# Hiveopolis.net
KiCad netlist of a schematic drawn in EAGLE
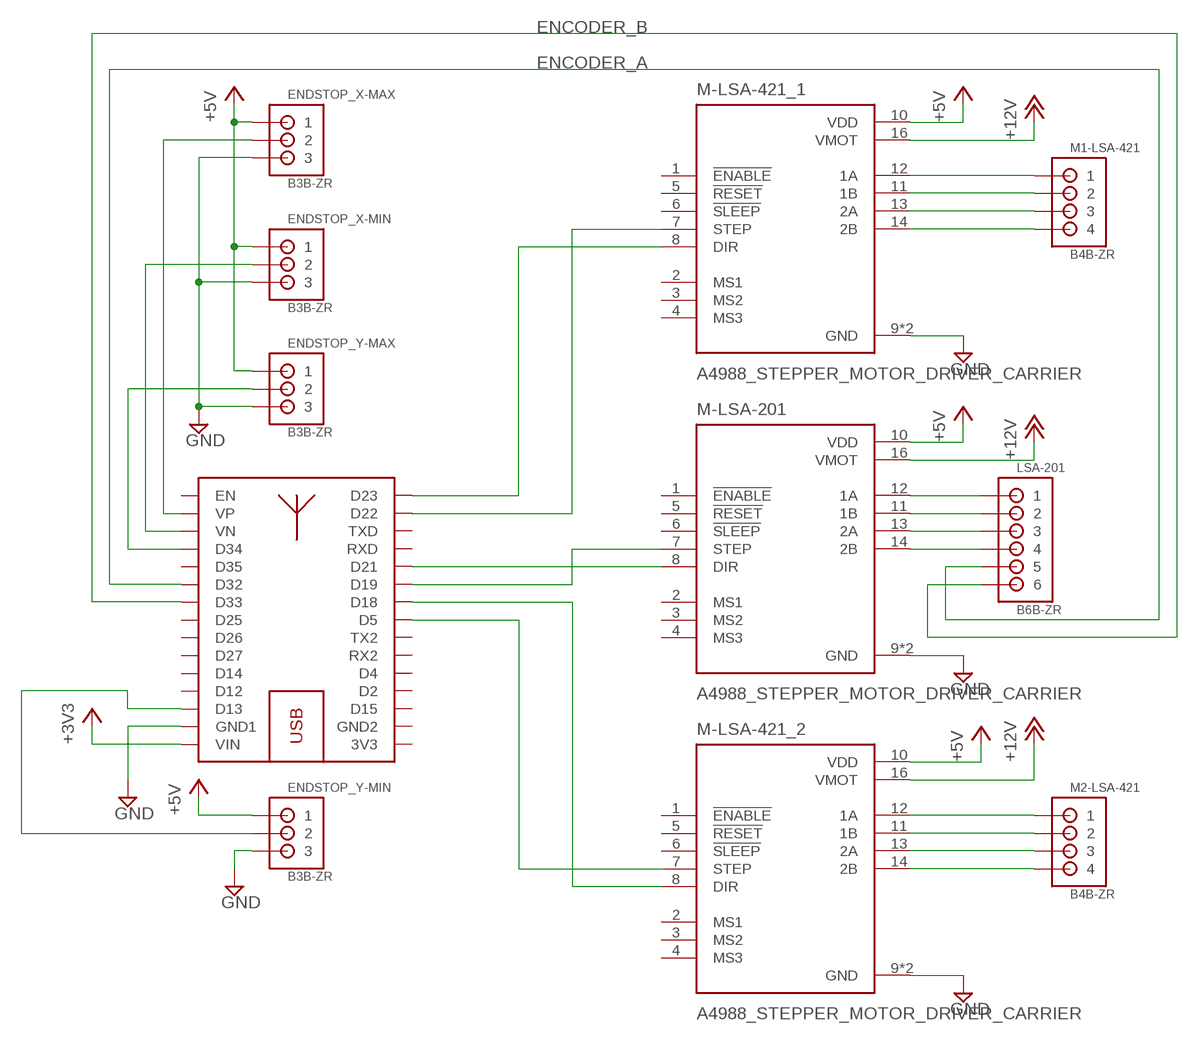
[diagram p0: schematic, sheet 1]

(export (version "E")
  (design (tool "Eeschema 10.0.6"))
  (components
    (comp (ref "ENDSTOP_X-MAX")
      (value "B3B-ZR")
      (footprint "eagle-import:B3B-ZR")
      (libsource (lib "eagle-import") (part "B3B-ZR"))
    )
    (comp (ref "ENDSTOP_X-MIN")
      (value "B3B-ZR")
      (footprint "eagle-import:B3B-ZR")
      (libsource (lib "eagle-import") (part "B3B-ZR"))
    )
    (comp (ref "ENDSTOP_Y-MAX")
      (value "B3B-ZR")
      (footprint "eagle-import:B3B-ZR")
      (libsource (lib "eagle-import") (part "B3B-ZR"))
    )
    (comp (ref "ENDSTOP_Y-MIN")
      (value "B3B-ZR")
      (footprint "eagle-import:B3B-ZR")
      (libsource (lib "eagle-import") (part "B3B-ZR"))
    )
    (comp (ref "LSA-201")
      (value "B6B-ZR")
      (footprint "eagle-import:B6B-ZR")
      (libsource (lib "eagle-import") (part "B6B-ZR"))
    )
    (comp (ref "M-LSA-201")
      (value "A4988_STEPPER_MOTOR_DRIVER_CARRIER")
      (footprint "eagle-import:MODULE_A4988_STEPPER_MOTOR_DRIVER_CARRIER")
      (fields (field (name "MF") "Pololu") (field (name "MP") "A4988 STEPPER MOTOR DRIVER CARRIER"))
      (libsource (lib "eagle-import") (part "A4988_STEPPER_MOTOR_DRIVER_CARRIER"))
    )
    (comp (ref "M-LSA-421_1")
      (value "A4988_STEPPER_MOTOR_DRIVER_CARRIER")
      (footprint "eagle-import:MODULE_A4988_STEPPER_MOTOR_DRIVER_CARRIER")
      (fields (field (name "MF") "Pololu") (field (name "MP") "A4988 STEPPER MOTOR DRIVER CARRIER"))
      (libsource (lib "eagle-import") (part "A4988_STEPPER_MOTOR_DRIVER_CARRIER"))
    )
    (comp (ref "M-LSA-421_2")
      (value "A4988_STEPPER_MOTOR_DRIVER_CARRIER")
      (footprint "eagle-import:MODULE_A4988_STEPPER_MOTOR_DRIVER_CARRIER")
      (fields (field (name "MF") "Pololu") (field (name "MP") "A4988 STEPPER MOTOR DRIVER CARRIER"))
      (libsource (lib "eagle-import") (part "A4988_STEPPER_MOTOR_DRIVER_CARRIER"))
    )
    (comp (ref "M1")
      (value "ESP32_DEVKIT_V1")
      (footprint "eagle-import:ARDUINO_NANO_V3")
      (fields (field (name "MF") "Do it") (field (name "MP") "ESP32 DEVKIT V1"))
      (libsource (lib "eagle-import") (part "ESP32_DEVKIT_V1"))
    )
    (comp (ref "M1-LSA-421")
      (value "B4B-ZR")
      (footprint "eagle-import:B4B-ZR")
      (libsource (lib "eagle-import") (part "B4B-ZR"))
    )
    (comp (ref "M2-LSA-421")
      (value "B4B-ZR")
      (footprint "eagle-import:B4B-ZR")
      (libsource (lib "eagle-import") (part "B4B-ZR"))
    )
  )
  (nets
    (net (code "1") (name "+3V3") (class "Default")
      (node (ref "M1") (pin "P$28") (pinfunction "VIN_P$28") (pintype "bidirectional"))
    )
    (net (code "2") (name "+5V") (class "Default")
      (node (ref "ENDSTOP_X-MAX") (pin "1") (pinfunction "1_1") (pintype "bidirectional"))
      (node (ref "ENDSTOP_X-MIN") (pin "1") (pinfunction "1_1") (pintype "bidirectional"))
      (node (ref "ENDSTOP_Y-MAX") (pin "1") (pinfunction "1_1") (pintype "bidirectional"))
      (node (ref "ENDSTOP_Y-MIN") (pin "1") (pinfunction "1_1") (pintype "bidirectional"))
      (node (ref "M-LSA-201") (pin "10") (pinfunction "VDD_10") (pintype "power_in"))
      (node (ref "M-LSA-421_1") (pin "10") (pinfunction "VDD_10") (pintype "power_in"))
      (node (ref "M-LSA-421_2") (pin "10") (pinfunction "VDD_10") (pintype "power_in"))
    )
    (net (code "3") (name "+12V") (class "Default")
      (node (ref "M-LSA-201") (pin "16") (pinfunction "VMOT_16") (pintype "power_in"))
      (node (ref "M-LSA-421_1") (pin "16") (pinfunction "VMOT_16") (pintype "power_in"))
      (node (ref "M-LSA-421_2") (pin "16") (pinfunction "VMOT_16") (pintype "power_in"))
    )
    (net (code "4") (name "/ENCODER_A") (class "Default")
      (node (ref "LSA-201") (pin "5") (pinfunction "5_5") (pintype "bidirectional"))
      (node (ref "M1") (pin "P$17") (pinfunction "D32_P$17") (pintype "bidirectional"))
    )
    (net (code "5") (name "/ENCODER_B") (class "Default")
      (node (ref "LSA-201") (pin "6") (pinfunction "6_6") (pintype "bidirectional"))
      (node (ref "M1") (pin "P$18") (pinfunction "D33_P$18") (pintype "bidirectional"))
    )
    (net (code "6") (name "GND") (class "Default")
      (node (ref "ENDSTOP_X-MAX") (pin "3") (pinfunction "3_3") (pintype "bidirectional"))
      (node (ref "ENDSTOP_X-MIN") (pin "3") (pinfunction "3_3") (pintype "bidirectional"))
      (node (ref "ENDSTOP_Y-MAX") (pin "3") (pinfunction "3_3") (pintype "bidirectional"))
      (node (ref "ENDSTOP_Y-MIN") (pin "3") (pinfunction "3_3") (pintype "bidirectional"))
      (node (ref "M-LSA-201") (pin "15") (pinfunction "GND_15") (pintype "power_in"))
      (node (ref "M-LSA-201") (pin "9") (pinfunction "GND_9") (pintype "power_in"))
      (node (ref "M-LSA-421_1") (pin "15") (pinfunction "GND_15") (pintype "power_in"))
      (node (ref "M-LSA-421_1") (pin "9") (pinfunction "GND_9") (pintype "power_in"))
      (node (ref "M-LSA-421_2") (pin "15") (pinfunction "GND_15") (pintype "power_in"))
      (node (ref "M-LSA-421_2") (pin "9") (pinfunction "GND_9") (pintype "power_in"))
      (node (ref "M1") (pin "P$22") (pinfunction "GND1_P$22") (pintype "bidirectional"))
    )
    (net (code "7") (name "Net-(M-LSA-201-1A)") (class "Default")
      (node (ref "LSA-201") (pin "1") (pinfunction "1_1") (pintype "bidirectional"))
      (node (ref "M-LSA-201") (pin "12") (pinfunction "1A_12") (pintype "output"))
    )
    (net (code "8") (name "Net-(M-LSA-201-1B)") (class "Default")
      (node (ref "LSA-201") (pin "2") (pinfunction "2_2") (pintype "bidirectional"))
      (node (ref "M-LSA-201") (pin "11") (pinfunction "1B_11") (pintype "output"))
    )
    (net (code "9") (name "Net-(M-LSA-201-2A)") (class "Default")
      (node (ref "LSA-201") (pin "3") (pinfunction "3_3") (pintype "bidirectional"))
      (node (ref "M-LSA-201") (pin "13") (pinfunction "2A_13") (pintype "output"))
    )
    (net (code "10") (name "Net-(M-LSA-201-2B)") (class "Default")
      (node (ref "LSA-201") (pin "4") (pinfunction "4_4") (pintype "bidirectional"))
      (node (ref "M-LSA-201") (pin "14") (pinfunction "2B_14") (pintype "output"))
    )
    (net (code "11") (name "Net-(M-LSA-201-DIR)") (class "Default")
      (node (ref "M-LSA-201") (pin "8") (pinfunction "DIR_8") (pintype "input"))
      (node (ref "M1") (pin "P$11") (pinfunction "D21_P$11") (pintype "bidirectional"))
    )
    (net (code "12") (name "Net-(M-LSA-201-STEP)") (class "Default")
      (node (ref "M-LSA-201") (pin "7") (pinfunction "STEP_7") (pintype "input"))
      (node (ref "M1") (pin "P$10") (pinfunction "D19_P$10") (pintype "bidirectional"))
    )
    (net (code "13") (name "Net-(M-LSA-421_1-1A)") (class "Default")
      (node (ref "M-LSA-421_1") (pin "12") (pinfunction "1A_12") (pintype "output"))
      (node (ref "M1-LSA-421") (pin "1") (pinfunction "1_1") (pintype "bidirectional"))
    )
    (net (code "14") (name "Net-(M-LSA-421_1-1B)") (class "Default")
      (node (ref "M-LSA-421_1") (pin "11") (pinfunction "1B_11") (pintype "output"))
      (node (ref "M1-LSA-421") (pin "2") (pinfunction "2_2") (pintype "bidirectional"))
    )
    (net (code "15") (name "Net-(M-LSA-421_1-2A)") (class "Default")
      (node (ref "M-LSA-421_1") (pin "13") (pinfunction "2A_13") (pintype "output"))
      (node (ref "M1-LSA-421") (pin "3") (pinfunction "3_3") (pintype "bidirectional"))
    )
    (net (code "16") (name "Net-(M-LSA-421_1-2B)") (class "Default")
      (node (ref "M-LSA-421_1") (pin "14") (pinfunction "2B_14") (pintype "output"))
      (node (ref "M1-LSA-421") (pin "4") (pinfunction "4_4") (pintype "bidirectional"))
    )
    (net (code "17") (name "Net-(M-LSA-421_1-DIR)") (class "Default")
      (node (ref "M-LSA-421_1") (pin "8") (pinfunction "DIR_8") (pintype "input"))
      (node (ref "M1") (pin "P$13") (pinfunction "D23_P$13") (pintype "bidirectional"))
    )
    (net (code "18") (name "Net-(M-LSA-421_1-STEP)") (class "Default")
      (node (ref "M-LSA-421_1") (pin "7") (pinfunction "STEP_7") (pintype "input"))
      (node (ref "M1") (pin "P$12") (pinfunction "D22_P$12") (pintype "bidirectional"))
    )
    (net (code "19") (name "Net-(M-LSA-421_2-1A)") (class "Default")
      (node (ref "M-LSA-421_2") (pin "12") (pinfunction "1A_12") (pintype "output"))
      (node (ref "M2-LSA-421") (pin "1") (pinfunction "1_1") (pintype "bidirectional"))
    )
    (net (code "20") (name "Net-(M-LSA-421_2-1B)") (class "Default")
      (node (ref "M-LSA-421_2") (pin "11") (pinfunction "1B_11") (pintype "output"))
      (node (ref "M2-LSA-421") (pin "2") (pinfunction "2_2") (pintype "bidirectional"))
    )
    (net (code "21") (name "Net-(M-LSA-421_2-2A)") (class "Default")
      (node (ref "M-LSA-421_2") (pin "13") (pinfunction "2A_13") (pintype "output"))
      (node (ref "M2-LSA-421") (pin "3") (pinfunction "3_3") (pintype "bidirectional"))
    )
    (net (code "22") (name "Net-(M-LSA-421_2-2B)") (class "Default")
      (node (ref "M-LSA-421_2") (pin "14") (pinfunction "2B_14") (pintype "output"))
      (node (ref "M2-LSA-421") (pin "4") (pinfunction "4_4") (pintype "bidirectional"))
    )
    (net (code "23") (name "Net-(M-LSA-421_2-DIR)") (class "Default")
      (node (ref "M-LSA-421_2") (pin "8") (pinfunction "DIR_8") (pintype "input"))
      (node (ref "M1") (pin "P$9") (pinfunction "D18_P$9") (pintype "bidirectional"))
    )
    (net (code "24") (name "Net-(M-LSA-421_2-STEP)") (class "Default")
      (node (ref "M-LSA-421_2") (pin "7") (pinfunction "STEP_7") (pintype "input"))
      (node (ref "M1") (pin "P$4") (pinfunction "D5_P$4") (pintype "bidirectional"))
    )
    (net (code "25") (name "Net-(M1-D13)") (class "Default")
      (node (ref "ENDSTOP_Y-MIN") (pin "2") (pinfunction "2_2") (pintype "bidirectional"))
      (node (ref "M1") (pin "P$6") (pinfunction "D13_P$6") (pintype "bidirectional"))
    )
    (net (code "26") (name "Net-(M1-D34)") (class "Default")
      (node (ref "ENDSTOP_Y-MAX") (pin "2") (pinfunction "2_2") (pintype "bidirectional"))
      (node (ref "M1") (pin "P$19") (pinfunction "D34_P$19") (pintype "bidirectional"))
    )
    (net (code "27") (name "Net-(M1-VN)") (class "Default")
      (node (ref "ENDSTOP_X-MIN") (pin "2") (pinfunction "2_2") (pintype "bidirectional"))
      (node (ref "M1") (pin "P$29") (pinfunction "VN_P$29") (pintype "bidirectional"))
    )
    (net (code "28") (name "Net-(M1-VP)") (class "Default")
      (node (ref "ENDSTOP_X-MAX") (pin "2") (pinfunction "2_2") (pintype "bidirectional"))
      (node (ref "M1") (pin "P$30") (pinfunction "VP_P$30") (pintype "bidirectional"))
    )
    (net (code "29") (name "unconnected-(M-LSA-201-MS1-Pad2)") (class "Default")
      (node (ref "M-LSA-201") (pin "2") (pinfunction "MS1_2") (pintype "input"))
    )
    (net (code "30") (name "unconnected-(M-LSA-201-MS2-Pad3)") (class "Default")
      (node (ref "M-LSA-201") (pin "3") (pinfunction "MS2_3") (pintype "input"))
    )
    (net (code "31") (name "unconnected-(M-LSA-201-MS3-Pad4)") (class "Default")
      (node (ref "M-LSA-201") (pin "4") (pinfunction "MS3_4") (pintype "input"))
    )
    (net (code "32") (name "unconnected-(M-LSA-201-~{ENABLE}-Pad1)") (class "Default")
      (node (ref "M-LSA-201") (pin "1") (pinfunction "~{ENABLE}_1") (pintype "input"))
    )
    (net (code "33") (name "unconnected-(M-LSA-201-~{RESET}-Pad5)") (class "Default")
      (node (ref "M-LSA-201") (pin "5") (pinfunction "~{RESET}_5") (pintype "input"))
    )
    (net (code "34") (name "unconnected-(M-LSA-201-~{SLEEP}-Pad6)") (class "Default")
      (node (ref "M-LSA-201") (pin "6") (pinfunction "~{SLEEP}_6") (pintype "input"))
    )
    (net (code "35") (name "unconnected-(M-LSA-421_1-MS1-Pad2)") (class "Default")
      (node (ref "M-LSA-421_1") (pin "2") (pinfunction "MS1_2") (pintype "input"))
    )
    (net (code "36") (name "unconnected-(M-LSA-421_1-MS2-Pad3)") (class "Default")
      (node (ref "M-LSA-421_1") (pin "3") (pinfunction "MS2_3") (pintype "input"))
    )
    (net (code "37") (name "unconnected-(M-LSA-421_1-MS3-Pad4)") (class "Default")
      (node (ref "M-LSA-421_1") (pin "4") (pinfunction "MS3_4") (pintype "input"))
    )
    (net (code "38") (name "unconnected-(M-LSA-421_1-~{ENABLE}-Pad1)") (class "Default")
      (node (ref "M-LSA-421_1") (pin "1") (pinfunction "~{ENABLE}_1") (pintype "input"))
    )
    (net (code "39") (name "unconnected-(M-LSA-421_1-~{RESET}-Pad5)") (class "Default")
      (node (ref "M-LSA-421_1") (pin "5") (pinfunction "~{RESET}_5") (pintype "input"))
    )
    (net (code "40") (name "unconnected-(M-LSA-421_1-~{SLEEP}-Pad6)") (class "Default")
      (node (ref "M-LSA-421_1") (pin "6") (pinfunction "~{SLEEP}_6") (pintype "input"))
    )
    (net (code "41") (name "unconnected-(M-LSA-421_2-MS1-Pad2)") (class "Default")
      (node (ref "M-LSA-421_2") (pin "2") (pinfunction "MS1_2") (pintype "input"))
    )
    (net (code "42") (name "unconnected-(M-LSA-421_2-MS2-Pad3)") (class "Default")
      (node (ref "M-LSA-421_2") (pin "3") (pinfunction "MS2_3") (pintype "input"))
    )
    (net (code "43") (name "unconnected-(M-LSA-421_2-MS3-Pad4)") (class "Default")
      (node (ref "M-LSA-421_2") (pin "4") (pinfunction "MS3_4") (pintype "input"))
    )
    (net (code "44") (name "unconnected-(M-LSA-421_2-~{ENABLE}-Pad1)") (class "Default")
      (node (ref "M-LSA-421_2") (pin "1") (pinfunction "~{ENABLE}_1") (pintype "input"))
    )
    (net (code "45") (name "unconnected-(M-LSA-421_2-~{RESET}-Pad5)") (class "Default")
      (node (ref "M-LSA-421_2") (pin "5") (pinfunction "~{RESET}_5") (pintype "input"))
    )
    (net (code "46") (name "unconnected-(M-LSA-421_2-~{SLEEP}-Pad6)") (class "Default")
      (node (ref "M-LSA-421_2") (pin "6") (pinfunction "~{SLEEP}_6") (pintype "input"))
    )
    (net (code "47") (name "unconnected-(M1-3V3-PadP$1)") (class "Default")
      (node (ref "M1") (pin "P$1") (pinfunction "3V3_P$1") (pintype "bidirectional"))
    )
    (net (code "48") (name "unconnected-(M1-D2-PadP$2)") (class "Default")
      (node (ref "M1") (pin "P$2") (pinfunction "D2_P$2") (pintype "bidirectional"))
    )
    (net (code "49") (name "unconnected-(M1-D4-PadP$3)") (class "Default")
      (node (ref "M1") (pin "P$3") (pinfunction "D4_P$3") (pintype "bidirectional"))
    )
    (net (code "50") (name "unconnected-(M1-D12-PadP$5)") (class "Default")
      (node (ref "M1") (pin "P$5") (pinfunction "D12_P$5") (pintype "bidirectional"))
    )
    (net (code "51") (name "unconnected-(M1-D14-PadP$7)") (class "Default")
      (node (ref "M1") (pin "P$7") (pinfunction "D14_P$7") (pintype "bidirectional"))
    )
    (net (code "52") (name "unconnected-(M1-D15-PadP$8)") (class "Default")
      (node (ref "M1") (pin "P$8") (pinfunction "D15_P$8") (pintype "bidirectional"))
    )
    (net (code "53") (name "unconnected-(M1-D25-PadP$14)") (class "Default")
      (node (ref "M1") (pin "P$14") (pinfunction "D25_P$14") (pintype "bidirectional"))
    )
    (net (code "54") (name "unconnected-(M1-D26-PadP$15)") (class "Default")
      (node (ref "M1") (pin "P$15") (pinfunction "D26_P$15") (pintype "bidirectional"))
    )
    (net (code "55") (name "unconnected-(M1-D27-PadP$16)") (class "Default")
      (node (ref "M1") (pin "P$16") (pinfunction "D27_P$16") (pintype "bidirectional"))
    )
    (net (code "56") (name "unconnected-(M1-D35-PadP$20)") (class "Default")
      (node (ref "M1") (pin "P$20") (pinfunction "D35_P$20") (pintype "bidirectional"))
    )
    (net (code "57") (name "unconnected-(M1-EN-PadP$21)") (class "Default")
      (node (ref "M1") (pin "P$21") (pinfunction "EN_P$21") (pintype "bidirectional"))
    )
    (net (code "58") (name "unconnected-(M1-GND2-PadP$23)") (class "Default")
      (node (ref "M1") (pin "P$23") (pinfunction "GND2_P$23") (pintype "bidirectional"))
    )
    (net (code "59") (name "unconnected-(M1-RX2-PadP$24)") (class "Default")
      (node (ref "M1") (pin "P$24") (pinfunction "RX2_P$24") (pintype "bidirectional"))
    )
    (net (code "60") (name "unconnected-(M1-RXD-PadP$25)") (class "Default")
      (node (ref "M1") (pin "P$25") (pinfunction "RXD_P$25") (pintype "bidirectional"))
    )
    (net (code "61") (name "unconnected-(M1-TX2-PadP$26)") (class "Default")
      (node (ref "M1") (pin "P$26") (pinfunction "TX2_P$26") (pintype "bidirectional"))
    )
    (net (code "62") (name "unconnected-(M1-TXD-PadP$27)") (class "Default")
      (node (ref "M1") (pin "P$27") (pinfunction "TXD_P$27") (pintype "bidirectional"))
    )
  )
)
